# ISPAdapter.net
KiCad netlist of a schematic drawn in EAGLE
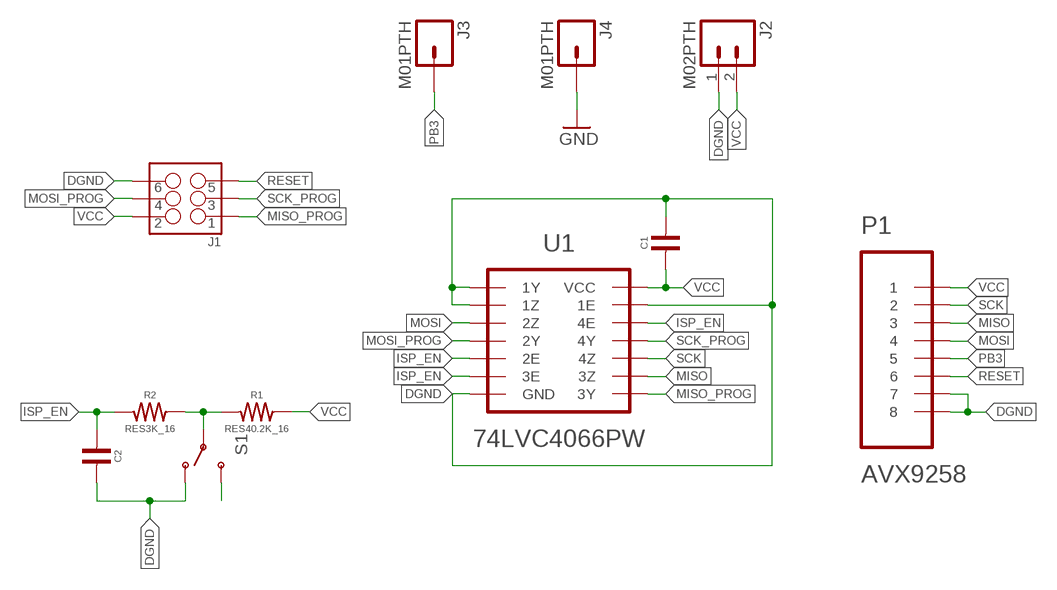
[diagram p0: schematic, sheet 1]

(export (version "E")
  (design (tool "Eeschema 10.0.6"))
  (components
    (comp (ref "C1")
      (value "CAP4.7UF_10V")
      (footprint "eagle-import:0402")
      (fields
        (field (name "DIGIKEY_PART_#") "445-13820-1-ND")
        (field (name "MANUFACTURER") "TDK Corporation")
        (field (name "MFG_PART_#") "C1005X5R1A475K050BC")
      )
      (libsource (lib "eagle-import") (part "CAP4.7UF_10V"))
    )
    (comp (ref "C2")
      (value "CAP0.1UF_100V")
      (footprint "eagle-import:0402")
      (fields
        (field (name "DIGIKEY_PART_#") "490-10458-1-ND")
        (field (name "MANUFACTURER") "Murata Electronics North America")
        (field (name "MFG_PART_#") "GRM155R62A104KE14D")
      )
      (libsource (lib "eagle-import") (part "CAP0.1UF_100V"))
    )
    (comp (ref "J1")
      (value "M03X2WR")
      (footprint "eagle-import:WR-BHD-3X2")
      (fields
        (field (name "DIGIKEY_PART_#") "732-5394-ND")
        (field (name "MANUFACTURER") "Wurth Electronics Inc")
        (field (name "MFG_PART_#") "61200621621")
      )
      (libsource (lib "eagle-import") (part "M03X2WR"))
    )
    (comp (ref "J2")
      (value "M02PTH")
      (footprint "eagle-import:1X02")
      (libsource (lib "eagle-import") (part "M02PTH"))
    )
    (comp (ref "J3")
      (value "M01PTH")
      (footprint "eagle-import:1X01")
      (libsource (lib "eagle-import") (part "M01PTH"))
    )
    (comp (ref "J4")
      (value "M01PTH")
      (footprint "eagle-import:1X01")
      (libsource (lib "eagle-import") (part "M01PTH"))
    )
    (comp (ref "P1")
      (value "AVX9258")
      (footprint "eagle-import:AVX9258-8C")
      (fields
        (field (name "DIGIKEY_PART_#") "478-5495-1-ND")
        (field (name "MANUFACTURER") "AVX Corporation")
        (field (name "MFG_PART_#") "009258008004063")
      )
      (libsource (lib "eagle-import") (part "AVX9258"))
    )
    (comp (ref "R1")
      (value "RES40.2K_16")
      (footprint "eagle-import:0402")
      (fields
        (field (name "DIGIKEY_PART_#") "541-40.2KLCT-ND")
        (field (name "MANUFACTURER") "Vishay Dale")
        (field (name "MFG_PART_#") "CRCW040240K2FKED")
      )
      (libsource (lib "eagle-import") (part "RES40.2K_16"))
    )
    (comp (ref "R2")
      (value "RES3K_16")
      (footprint "eagle-import:0402")
      (fields
        (field (name "DIGIKEY_PART_#") "541-3.00KLCT-ND")
        (field (name "MANUFACTURER") "Vishay Dale")
        (field (name "MFG_PART_#") "CRCW04023K00FKED")
      )
      (libsource (lib "eagle-import") (part "RES3K_16"))
    )
    (comp (ref "S1")
      (value "SWITCH-SPDTESWITCH")
      (footprint "eagle-import:EG1271A")
      (fields
        (field (name "DIGIKEY_PART_#") "EG1919-ND")
        (field (name "MANUFACTURER") "E-Switch")
        (field (name "MFG_PART_#") "EG1271A")
      )
      (libsource (lib "eagle-import") (part "SWITCH-SPDTESWITCH"))
    )
    (comp (ref "U1")
      (value "74LVC4066PW")
      (footprint "eagle-import:14-TSSOP")
      (fields
        (field (name "DIGIKEY_PART_#") "568-3021-5-ND")
        (field (name "MANUFACTURER") "NXP Semiconductors")
        (field (name "MFG_PART_#") "74LVC4066PW,112")
      )
      (libsource (lib "eagle-import") (part "74LVC4066PW"))
    )
  )
  (nets
    (net (code "1") (name "DGND") (class "Default")
      (node (ref "C1") (pin "2") (pinfunction "2_2") (pintype "passive"))
      (node (ref "C2") (pin "2") (pinfunction "2_2") (pintype "passive"))
      (node (ref "J1") (pin "6") (pinfunction "6_6") (pintype "bidirectional"))
      (node (ref "J2") (pin "1") (pinfunction "1_1") (pintype "passive"))
      (node (ref "P1") (pin "7") (pinfunction "7_7") (pintype "passive"))
      (node (ref "P1") (pin "8") (pinfunction "8_8") (pintype "passive"))
      (node (ref "S1") (pin "1") (pinfunction "O_1") (pintype "passive"))
      (node (ref "S1") (pin "4") (pinfunction "O_4") (pintype "passive"))
      (node (ref "U1") (pin "1") (pinfunction "1Y_1") (pintype "passive"))
      (node (ref "U1") (pin "13") (pinfunction "1E_13") (pintype "passive"))
      (node (ref "U1") (pin "2") (pinfunction "1Z_2") (pintype "passive"))
      (node (ref "U1") (pin "7") (pinfunction "GND_7") (pintype "passive"))
    )
    (net (code "2") (name "GND") (class "Default")
      (node (ref "J4") (pin "1") (pinfunction "1_1") (pintype "passive"))
    )
    (net (code "3") (name "ISP_EN") (class "Default")
      (node (ref "C2") (pin "1") (pinfunction "1_1") (pintype "passive"))
      (node (ref "R2") (pin "1") (pinfunction "1_1") (pintype "passive"))
      (node (ref "U1") (pin "12") (pinfunction "4E_12") (pintype "passive"))
      (node (ref "U1") (pin "5") (pinfunction "2E_5") (pintype "passive"))
      (node (ref "U1") (pin "6") (pinfunction "3E_6") (pintype "passive"))
    )
    (net (code "4") (name "MISO") (class "Default")
      (node (ref "P1") (pin "3") (pinfunction "3_3") (pintype "passive"))
      (node (ref "U1") (pin "9") (pinfunction "3Z_9") (pintype "passive"))
    )
    (net (code "5") (name "MISO_PROG") (class "Default")
      (node (ref "J1") (pin "1") (pinfunction "1_1") (pintype "bidirectional"))
      (node (ref "U1") (pin "8") (pinfunction "3Y_8") (pintype "passive"))
    )
    (net (code "6") (name "MOSI") (class "Default")
      (node (ref "P1") (pin "4") (pinfunction "4_4") (pintype "passive"))
      (node (ref "U1") (pin "3") (pinfunction "2Z_3") (pintype "passive"))
    )
    (net (code "7") (name "MOSI_PROG") (class "Default")
      (node (ref "J1") (pin "4") (pinfunction "4_4") (pintype "bidirectional"))
      (node (ref "U1") (pin "4") (pinfunction "2Y_4") (pintype "passive"))
    )
    (net (code "8") (name "Net-(R1-Pad1)") (class "Default")
      (node (ref "R1") (pin "1") (pinfunction "1_1") (pintype "passive"))
      (node (ref "R2") (pin "2") (pinfunction "2_2") (pintype "passive"))
      (node (ref "S1") (pin "2") (pinfunction "P_2") (pintype "passive"))
      (node (ref "S1") (pin "5") (pinfunction "P_5") (pintype "passive"))
    )
    (net (code "9") (name "Net-(S1-S-Pad3)") (class "Default")
      (node (ref "S1") (pin "3") (pinfunction "S_3") (pintype "passive"))
      (node (ref "S1") (pin "6") (pinfunction "S_6") (pintype "passive"))
    )
    (net (code "10") (name "PB3") (class "Default")
      (node (ref "J3") (pin "1") (pinfunction "1_1") (pintype "passive"))
      (node (ref "P1") (pin "5") (pinfunction "5_5") (pintype "passive"))
    )
    (net (code "11") (name "RESET") (class "Default")
      (node (ref "J1") (pin "5") (pinfunction "5_5") (pintype "bidirectional"))
      (node (ref "P1") (pin "6") (pinfunction "6_6") (pintype "passive"))
    )
    (net (code "12") (name "SCK") (class "Default")
      (node (ref "P1") (pin "2") (pinfunction "2_2") (pintype "passive"))
      (node (ref "U1") (pin "10") (pinfunction "4Z_10") (pintype "passive"))
    )
    (net (code "13") (name "SCK_PROG") (class "Default")
      (node (ref "J1") (pin "3") (pinfunction "3_3") (pintype "bidirectional"))
      (node (ref "U1") (pin "11") (pinfunction "4Y_11") (pintype "passive"))
    )
    (net (code "14") (name "VCC") (class "Default")
      (node (ref "C1") (pin "1") (pinfunction "1_1") (pintype "passive"))
      (node (ref "J1") (pin "2") (pinfunction "2_2") (pintype "bidirectional"))
      (node (ref "J2") (pin "2") (pinfunction "2_2") (pintype "passive"))
      (node (ref "P1") (pin "1") (pinfunction "1_1") (pintype "passive"))
      (node (ref "R1") (pin "2") (pinfunction "2_2") (pintype "passive"))
      (node (ref "U1") (pin "14") (pinfunction "VCC_14") (pintype "passive"))
    )
  )
)
